# MCU.net
KiCad netlist of a schematic drawn in Altium Designer
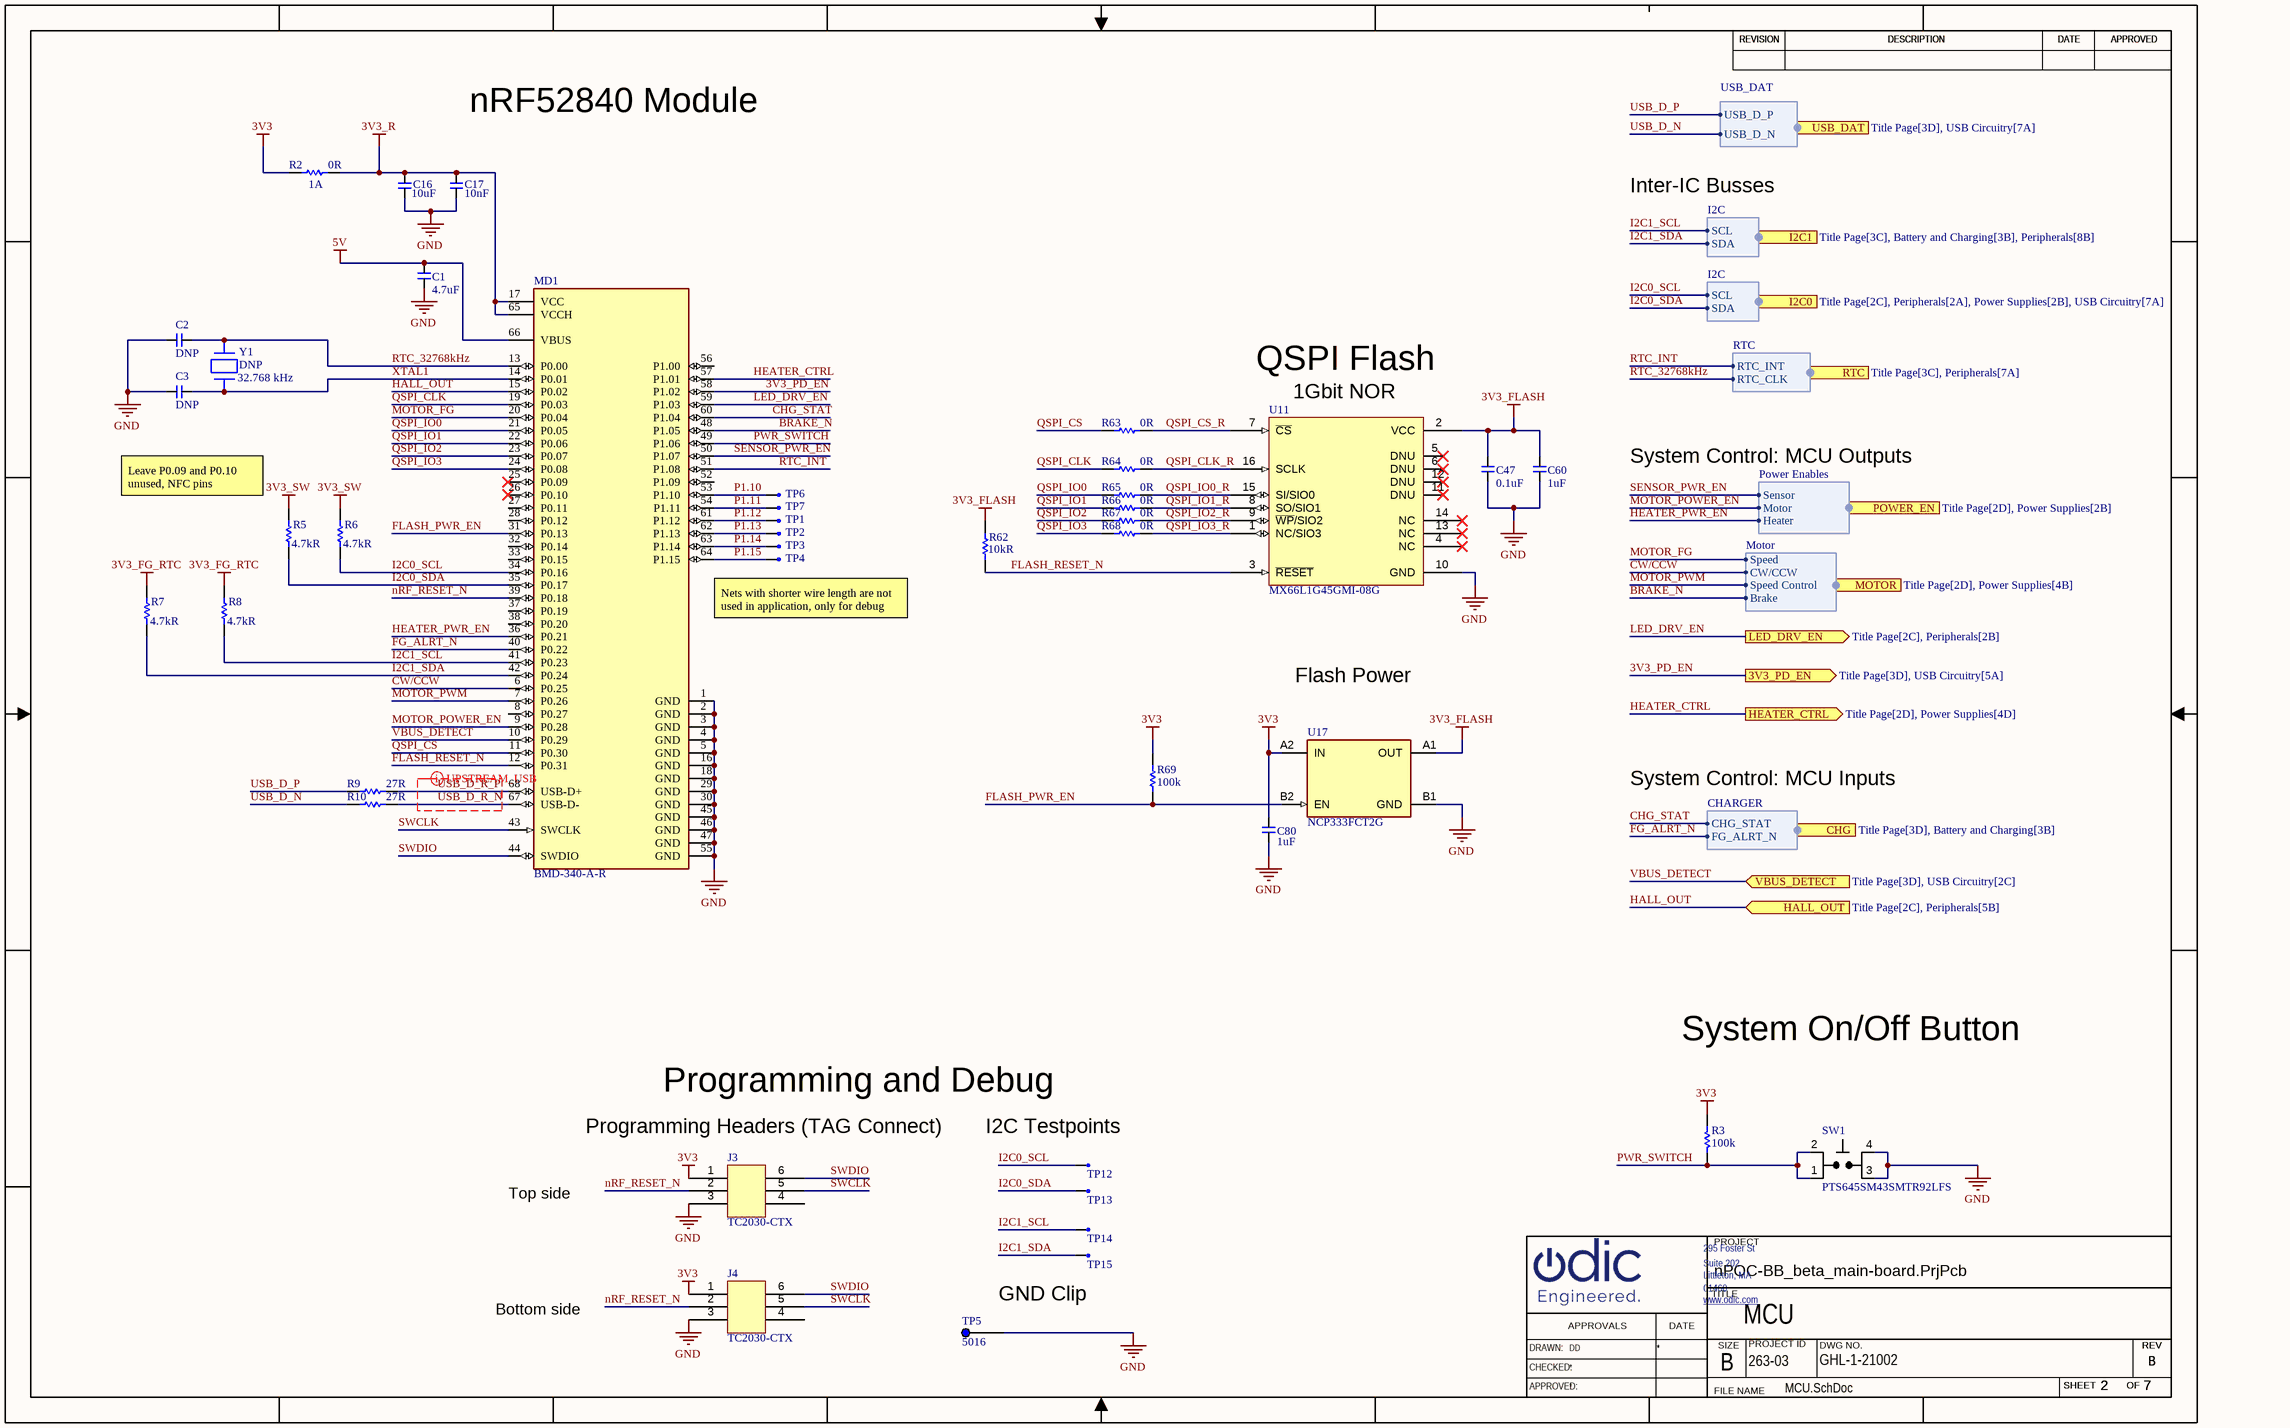
[diagram p0: MCU.SchDoc]

(export (version "E")
  (design (tool "Eeschema 10.0.6"))
  (components
    (comp (ref "C1")
      (value "4.7uF")
      (footprint "C0603")
      (description "CAP CER 4.7UF 25V X5R 0603")
      (fields (field (name "TOLERANCE") "20%"))
      (libsource (lib "Odic Inc") (part "cAP"))
    )
    (comp (ref "C2")
      (value "DNP")
      (footprint "C0402")
      (description "Blank pads for future cap placements")
      (libsource (lib "Odic Inc") (part "cAP"))
    )
    (comp (ref "C3")
      (value "DNP")
      (footprint "C0402")
      (description "Blank pads for future cap placements")
      (libsource (lib "Odic Inc") (part "cAP"))
    )
    (comp (ref "C16")
      (value "C0402_10u_6V3_20pct")
      (footprint "C0402")
      (description "Cap Ceramic 10uF 6.3V X5R 20% SMD 0402 85°C Paper T/R")
      (fields (field (name "CAPACITANCE") "10uF") (field (name "TOLERANCE") "20%"))
      (libsource (lib "Odic Inc") (part "cAP"))
    )
    (comp (ref "C17")
      (value "C0402_10n_6V3_10pct")
      (footprint "C0402")
      (description "CAP CER 10000PF 25V 10% X7R 0402")
      (fields
        (field (name "TOLERANCE") "10%")
        (field (name "CAPACITANCE") "10nF")
        (field (name "VOLTAGE") "25V")
      )
      (libsource (lib "Odic Inc") (part "cAP"))
    )
    (comp (ref "C47")
      (value "0.1uF")
      (footprint "C0402")
      (description "Cap Ceramic 0.1uF 25V X5R 10% Pad SMD 0402 Multi Layer Ceramic Capacitor (MLCC)")
      (fields (field (name "VOLTAGE") "25V") (field (name "TOLERANCE") "10%"))
      (libsource (lib "Odic Inc") (part "cAP"))
    )
    (comp (ref "C60")
      (value "1uF")
      (footprint "C0402")
      (description "CAP CER 1UF 16V X5R 0402")
      (fields (field (name "VOLTAGE") "16V") (field (name "TOLERANCE") "10%"))
      (libsource (lib "Odic Inc") (part "cAP"))
    )
    (comp (ref "C80")
      (value "C0402_1u_6V3_10pct")
      (footprint "C0402")
      (description "Cap Ceramic 1uF 6.3V X5R 10% SMD 0402 85C Paper T/R")
      (fields (field (name "CAPACITANCE") "1uF") (field (name "TOLERANCE") "10%"))
      (libsource (lib "Odic Inc") (part "cAP"))
    )
    (comp (ref "J3")
      (value "TC2030-CTX")
      (footprint "tc2030-ctx")
      (description "Cbl Plug-of-nails to Cortex Swd")
      (libsource (lib "Odic Inc") (part "TC2030-CTX-Symbol-1"))
    )
    (comp (ref "J4")
      (value "TC2030-CTX")
      (footprint "tc2030-ctx")
      (description "Cbl Plug-of-nails to Cortex Swd")
      (libsource (lib "Odic Inc") (part "TC2030-CTX-Symbol-1"))
    )
    (comp (ref "MD1")
      (value "BMD-340-A-R")
      (footprint "BMD-340-A-R")
      (description "BMD-340 Series 3.6 V 2.5 GHz -96 dBm Stand-Alone Bluetooth 5 Low Energy Module")
      (fields (field (name "MP") "BMD-330-A-R"))
      (libsource (lib "Odic Inc") (part "91e469dc995d0ea2fa1e7beafcd1398"))
    )
    (comp (ref "R2")
      (value "R0603_0R")
      (footprint "R0603")
      (description "Res Thkflm 0603 0 Ohm Jumper 1/10W 100Ppm/ C Smd Rohs Compliant: Yes")
      (fields (field (name "RESISTANCE") "0R") (field (name "CURRENT RATING") "1A"))
      (libsource (lib "Odic Inc") (part "RES"))
    )
    (comp (ref "R3")
      (value "100k")
      (footprint "R0402")
      (description "Res General Purpose Thick Film 0402 100K Ohm 1% 1/16W ±100ppm/°C Molded SMD Paper T/R")
      (fields (field (name "TOLERANCE") "1%"))
      (libsource (lib "Odic Inc") (part "RES"))
    )
    (comp (ref "R5")
      (value "R0402_4k7_1pct")
      (footprint "R0402")
      (description "RES 4.7K OHM 1% 1/16W 0402")
      (fields (field (name "TOLERANCE") "1%") (field (name "RESISTANCE") "4.7kR"))
      (libsource (lib "Odic Inc") (part "RES"))
    )
    (comp (ref "R6")
      (value "R0402_4k7_1pct")
      (footprint "R0402")
      (description "RES 4.7K OHM 1% 1/16W 0402")
      (fields (field (name "TOLERANCE") "1%") (field (name "RESISTANCE") "4.7kR"))
      (libsource (lib "Odic Inc") (part "RES"))
    )
    (comp (ref "R7")
      (value "R0402_4k7_1pct")
      (footprint "R0402")
      (description "RES 4.7K OHM 1% 1/16W 0402")
      (fields (field (name "TOLERANCE") "1%") (field (name "RESISTANCE") "4.7kR"))
      (libsource (lib "Odic Inc") (part "RES"))
    )
    (comp (ref "R8")
      (value "R0402_4k7_1pct")
      (footprint "R0402")
      (description "RES 4.7K OHM 1% 1/16W 0402")
      (fields (field (name "TOLERANCE") "1%") (field (name "RESISTANCE") "4.7kR"))
      (libsource (lib "Odic Inc") (part "RES"))
    )
    (comp (ref "R9")
      (value "27R")
      (footprint "R0402")
      (description "SMD Chip Resistor, 27 Ohm, ± 1%, 100 mW, 0402 [1005 Metric], Thick Film, Precision")
      (fields (field (name "TOLERANCE") "1%"))
      (libsource (lib "Odic Inc") (part "RES"))
    )
    (comp (ref "R10")
      (value "27R")
      (footprint "R0402")
      (description "SMD Chip Resistor, 27 Ohm, ± 1%, 100 mW, 0402 [1005 Metric], Thick Film, Precision")
      (fields (field (name "TOLERANCE") "1%"))
      (libsource (lib "Odic Inc") (part "RES"))
    )
    (comp (ref "R62")
      (value "R0402_10k_1pct")
      (footprint "R0402")
      (description "Res Thick Film 0402 10K Ohm 1% 1/16W ±100ppm/°C Molded SMD SMD T/R")
      (fields (field (name "RESISTANCE") "10kR") (field (name "TOLERANCE") "1%"))
      (libsource (lib "Odic Inc") (part "RES"))
    )
    (comp (ref "R63")
      (value "0R")
      (footprint "R0402")
      (description "RES 0 OHM JUMPER 1/16W 0402")
      (libsource (lib "Odic Inc") (part "RES"))
    )
    (comp (ref "R64")
      (value "0R")
      (footprint "R0402")
      (description "RES 0 OHM JUMPER 1/16W 0402")
      (libsource (lib "Odic Inc") (part "RES"))
    )
    (comp (ref "R65")
      (value "0R")
      (footprint "R0402")
      (description "RES 0 OHM JUMPER 1/16W 0402")
      (libsource (lib "Odic Inc") (part "RES"))
    )
    (comp (ref "R66")
      (value "0R")
      (footprint "R0402")
      (description "RES 0 OHM JUMPER 1/16W 0402")
      (libsource (lib "Odic Inc") (part "RES"))
    )
    (comp (ref "R67")
      (value "0R")
      (footprint "R0402")
      (description "RES 0 OHM JUMPER 1/16W 0402")
      (libsource (lib "Odic Inc") (part "RES"))
    )
    (comp (ref "R68")
      (value "0R")
      (footprint "R0402")
      (description "RES 0 OHM JUMPER 1/16W 0402")
      (libsource (lib "Odic Inc") (part "RES"))
    )
    (comp (ref "R69")
      (value "100k")
      (footprint "R0402")
      (description "Res General Purpose Thick Film 0402 100K Ohm 1% 1/16W ±100ppm/°C Molded SMD Paper T/R")
      (fields (field (name "TOLERANCE") "1%"))
      (libsource (lib "Odic Inc") (part "RES"))
    )
    (comp (ref "SW1")
      (value "PTS645SM43SMTR92LFS")
      (footprint "swt_pb_pts645s")
      (description "Switch Tactile N.O. SPST Round Button Gull Wing 0.05A 12VDC 100000Cycles 1.57N SMD T/R")
      (libsource (lib "Odic Inc") (part "TL3315NF160Q-Symbol-1"))
    )
    (comp (ref "TP1")
      (value "TPC30")
      (footprint "tpc30")
      (description "Test Point Circle 30")
      (libsource (lib "Odic Inc") (part "TPC"))
    )
    (comp (ref "TP2")
      (value "TPC30")
      (footprint "tpc30")
      (description "Test Point Circle 30")
      (libsource (lib "Odic Inc") (part "TPC"))
    )
    (comp (ref "TP3")
      (value "TPC30")
      (footprint "tpc30")
      (description "Test Point Circle 30")
      (libsource (lib "Odic Inc") (part "TPC"))
    )
    (comp (ref "TP4")
      (value "TPC30")
      (footprint "tpc30")
      (description "Test Point Circle 30")
      (libsource (lib "Odic Inc") (part "TPC"))
    )
    (comp (ref "TP5")
      (value "5016")
      (footprint "KEYSTONE_5016")
      (description "Test point clip, SMT Phos Bronze/Silver 1000pc Tape & Reel")
      (libsource (lib "Odic Inc") (part "5016-Symbol-1"))
    )
    (comp (ref "TP6")
      (value "TPC30")
      (footprint "tpc30")
      (description "Test Point Circle 30")
      (libsource (lib "Odic Inc") (part "TPC"))
    )
    (comp (ref "TP7")
      (value "TPC30")
      (footprint "tpc30")
      (description "Test Point Circle 30")
      (libsource (lib "Odic Inc") (part "TPC"))
    )
    (comp (ref "TP12")
      (value "TPC30")
      (footprint "tpc30")
      (description "Test Point Circle 30")
      (libsource (lib "Odic Inc") (part "TPC"))
    )
    (comp (ref "TP13")
      (value "TPC30")
      (footprint "tpc30")
      (description "Test Point Circle 30")
      (libsource (lib "Odic Inc") (part "TPC"))
    )
    (comp (ref "TP14")
      (value "TPC30")
      (footprint "tpc30")
      (description "Test Point Circle 30")
      (libsource (lib "Odic Inc") (part "TPC"))
    )
    (comp (ref "TP15")
      (value "TPC30")
      (footprint "tpc30")
      (description "Test Point Circle 30")
      (libsource (lib "Odic Inc") (part "TPC"))
    )
    (comp (ref "U11")
      (value "MX66L1G45GMI-08G")
      (footprint "sol16")
      (description "MX66L1G45G Series 1 Gb (1 G x 1) 2.7 - 3.6 V SMT Serial Flash Memory - SOP-16")
      (libsource (lib "Odic Inc") (part "MX66L1G45GMI-08G-Symbol-1"))
    )
    (comp (ref "U17")
      (value "NCP333FCT2G")
      (footprint "bga4_p743xp743_p4mm")
      (description "IC LOAD SWITCH W/DIS 1.5A 4WLCSP")
      (libsource (lib "Odic Inc") (part "97019fd276bc7644be76e1f711e9589"))
    )
    (comp (ref "Y1")
      (value "DNP")
      (footprint "xtal2_3p2x1p5")
      (description "RT3215 Series 0.032768 ±20 ppm 9pF -40°C TO +85°C SMT Tuning Fork Crystal")
      (fields (field (name "OPERATING FREQUENCY") "32.768 kHz"))
      (libsource (lib "Odic Inc") (part "Y*"))
    )
  )
  (nets
    (net (code "8") (name "/3V3_PD_EN") (class "Default")
      (node (ref "MD1") (pin "58") (pinfunction "P1.02_58") (pintype "bidirectional"))
    )
    (net (code "9") (name "/BRAKE_N") (class "Default")
      (node (ref "MD1") (pin "48") (pinfunction "P1.05_48") (pintype "bidirectional"))
    )
    (net (code "10") (name "/CHG_STAT") (class "Default")
      (node (ref "MD1") (pin "60") (pinfunction "P1.04_60") (pintype "bidirectional"))
    )
    (net (code "11") (name "/CW{slash}CCW") (class "Default")
      (node (ref "MD1") (pin "6") (pinfunction "P0.25_6") (pintype "bidirectional"))
    )
    (net (code "12") (name "/FG_ALRT_N") (class "Default")
      (node (ref "MD1") (pin "40") (pinfunction "P0.22_40") (pintype "bidirectional"))
    )
    (net (code "13") (name "/FLASH_PWR_EN") (class "Default")
      (node (ref "MD1") (pin "31") (pinfunction "P0.13_31") (pintype "bidirectional"))
      (node (ref "R69") (pin "2") (pinfunction "2_2") (pintype "passive"))
      (node (ref "U17") (pin "B2") (pinfunction "EN_B2") (pintype "input"))
    )
    (net (code "14") (name "/FLASH_RESET_N") (class "Default")
      (node (ref "MD1") (pin "12") (pinfunction "P0.31_12") (pintype "bidirectional"))
      (node (ref "R62") (pin "2") (pinfunction "2_2") (pintype "passive"))
      (node (ref "U11") (pin "3") (pinfunction "~{RESET}_3") (pintype "input"))
    )
    (net (code "15") (name "/HALL_OUT") (class "Default")
      (node (ref "MD1") (pin "15") (pinfunction "P0.02_15") (pintype "bidirectional"))
    )
    (net (code "16") (name "/HEATER_CTRL") (class "Default")
      (node (ref "MD1") (pin "57") (pinfunction "P1.01_57") (pintype "bidirectional"))
    )
    (net (code "17") (name "/HEATER_PWR_EN") (class "Default")
      (node (ref "MD1") (pin "36") (pinfunction "P0.21_36") (pintype "bidirectional"))
    )
    (net (code "18") (name "/I2C0_SCL") (class "Default")
      (node (ref "MD1") (pin "34") (pinfunction "P0.16_34") (pintype "bidirectional"))
      (node (ref "R6") (pin "1") (pinfunction "1_1") (pintype "passive"))
      (node (ref "TP12") (pin "1") (pinfunction "1_1") (pintype "passive"))
    )
    (net (code "19") (name "/I2C0_SDA") (class "Default")
      (node (ref "MD1") (pin "35") (pinfunction "P0.17_35") (pintype "bidirectional"))
      (node (ref "R5") (pin "1") (pinfunction "1_1") (pintype "passive"))
      (node (ref "TP13") (pin "1") (pinfunction "1_1") (pintype "passive"))
    )
    (net (code "20") (name "/I2C1_SCL") (class "Default")
      (node (ref "MD1") (pin "41") (pinfunction "P0.23_41") (pintype "bidirectional"))
      (node (ref "R8") (pin "1") (pinfunction "1_1") (pintype "passive"))
      (node (ref "TP14") (pin "1") (pinfunction "1_1") (pintype "passive"))
    )
    (net (code "21") (name "/I2C1_SDA") (class "Default")
      (node (ref "MD1") (pin "42") (pinfunction "P0.24_42") (pintype "bidirectional"))
      (node (ref "R7") (pin "1") (pinfunction "1_1") (pintype "passive"))
      (node (ref "TP15") (pin "1") (pinfunction "1_1") (pintype "passive"))
    )
    (net (code "22") (name "/LED_DRV_EN") (class "Default")
      (node (ref "MD1") (pin "59") (pinfunction "P1.03_59") (pintype "bidirectional"))
    )
    (net (code "23") (name "/MOTOR_FG") (class "Default")
      (node (ref "MD1") (pin "20") (pinfunction "P0.04_20") (pintype "bidirectional"))
    )
    (net (code "24") (name "/MOTOR_POWER_EN") (class "Default")
      (node (ref "MD1") (pin "9") (pinfunction "P0.28_9") (pintype "bidirectional"))
    )
    (net (code "25") (name "/MOTOR_PWM") (class "Default")
      (node (ref "MD1") (pin "7") (pinfunction "P0.26_7") (pintype "bidirectional"))
    )
    (net (code "26") (name "/P1.10") (class "Default")
      (node (ref "MD1") (pin "53") (pinfunction "P1.10_53") (pintype "bidirectional"))
      (node (ref "TP6") (pin "1") (pinfunction "1_1") (pintype "passive"))
    )
    (net (code "27") (name "/P1.11") (class "Default")
      (node (ref "MD1") (pin "54") (pinfunction "P1.11_54") (pintype "bidirectional"))
      (node (ref "TP7") (pin "1") (pinfunction "1_1") (pintype "passive"))
    )
    (net (code "28") (name "/P1.12") (class "Default")
      (node (ref "MD1") (pin "61") (pinfunction "P1.12_61") (pintype "bidirectional"))
      (node (ref "TP1") (pin "1") (pinfunction "1_1") (pintype "passive"))
    )
    (net (code "29") (name "/P1.13") (class "Default")
      (node (ref "MD1") (pin "62") (pinfunction "P1.13_62") (pintype "bidirectional"))
      (node (ref "TP2") (pin "1") (pinfunction "1_1") (pintype "passive"))
    )
    (net (code "30") (name "/P1.14") (class "Default")
      (node (ref "MD1") (pin "63") (pinfunction "P1.14_63") (pintype "bidirectional"))
      (node (ref "TP3") (pin "1") (pinfunction "1_1") (pintype "passive"))
    )
    (net (code "31") (name "/P1.15") (class "Default")
      (node (ref "MD1") (pin "64") (pinfunction "P1.15_64") (pintype "bidirectional"))
      (node (ref "TP4") (pin "1") (pinfunction "1_1") (pintype "passive"))
    )
    (net (code "32") (name "/PWR_SWITCH") (class "Default")
      (node (ref "MD1") (pin "49") (pinfunction "P1.06_49") (pintype "bidirectional"))
      (node (ref "R3") (pin "1") (pinfunction "1_1") (pintype "passive"))
      (node (ref "SW1") (pin "1") (pinfunction "1_1") (pintype "passive"))
      (node (ref "SW1") (pin "2") (pinfunction "2_2") (pintype "passive"))
    )
    (net (code "33") (name "/QSPI_CLK") (class "Default")
      (node (ref "MD1") (pin "19") (pinfunction "P0.03_19") (pintype "bidirectional"))
      (node (ref "R64") (pin "1") (pinfunction "1_1") (pintype "passive"))
    )
    (net (code "34") (name "/QSPI_CLK_R") (class "Default")
      (node (ref "R64") (pin "2") (pinfunction "2_2") (pintype "passive"))
      (node (ref "U11") (pin "16") (pinfunction "SCLK_16") (pintype "input"))
    )
    (net (code "35") (name "/QSPI_CS") (class "Default")
      (node (ref "MD1") (pin "11") (pinfunction "P0.30_11") (pintype "bidirectional"))
      (node (ref "R63") (pin "1") (pinfunction "1_1") (pintype "passive"))
    )
    (net (code "36") (name "/QSPI_CS_R") (class "Default")
      (node (ref "R63") (pin "2") (pinfunction "2_2") (pintype "passive"))
      (node (ref "U11") (pin "7") (pinfunction "~{CS}_7") (pintype "input"))
    )
    (net (code "37") (name "/QSPI_IO0") (class "Default")
      (node (ref "MD1") (pin "21") (pinfunction "P0.05_21") (pintype "bidirectional"))
      (node (ref "R65") (pin "1") (pinfunction "1_1") (pintype "passive"))
    )
    (net (code "38") (name "/QSPI_IO0_R") (class "Default")
      (node (ref "R65") (pin "2") (pinfunction "2_2") (pintype "passive"))
      (node (ref "U11") (pin "15") (pinfunction "SI/SIO0_15") (pintype "bidirectional"))
    )
    (net (code "39") (name "/QSPI_IO1") (class "Default")
      (node (ref "MD1") (pin "22") (pinfunction "P0.06_22") (pintype "bidirectional"))
      (node (ref "R66") (pin "1") (pinfunction "1_1") (pintype "passive"))
    )
    (net (code "40") (name "/QSPI_IO1_R") (class "Default")
      (node (ref "R66") (pin "2") (pinfunction "2_2") (pintype "passive"))
      (node (ref "U11") (pin "8") (pinfunction "SO/SIO1_8") (pintype "bidirectional"))
    )
    (net (code "41") (name "/QSPI_IO2") (class "Default")
      (node (ref "MD1") (pin "23") (pinfunction "P0.07_23") (pintype "bidirectional"))
      (node (ref "R67") (pin "1") (pinfunction "1_1") (pintype "passive"))
    )
    (net (code "42") (name "/QSPI_IO2_R") (class "Default")
      (node (ref "R67") (pin "2") (pinfunction "2_2") (pintype "passive"))
      (node (ref "U11") (pin "9") (pinfunction "~{WP}/SIO2_9") (pintype "bidirectional"))
    )
    (net (code "43") (name "/QSPI_IO3") (class "Default")
      (node (ref "MD1") (pin "24") (pinfunction "P0.08_24") (pintype "bidirectional"))
      (node (ref "R68") (pin "1") (pinfunction "1_1") (pintype "passive"))
    )
    (net (code "44") (name "/QSPI_IO3_R") (class "Default")
      (node (ref "R68") (pin "2") (pinfunction "2_2") (pintype "passive"))
      (node (ref "U11") (pin "1") (pinfunction "NC/SIO3_1") (pintype "bidirectional"))
    )
    (net (code "45") (name "/RTC_32768kHz") (class "Default")
      (node (ref "C2") (pin "2") (pinfunction "2_2") (pintype "passive"))
      (node (ref "MD1") (pin "13") (pinfunction "P0.00_13") (pintype "bidirectional"))
      (node (ref "Y1") (pin "1") (pinfunction "1_1") (pintype "passive"))
    )
    (net (code "46") (name "/RTC_INT") (class "Default")
      (node (ref "MD1") (pin "51") (pinfunction "P1.08_51") (pintype "bidirectional"))
    )
    (net (code "47") (name "/SENSOR_PWR_EN") (class "Default")
      (node (ref "MD1") (pin "50") (pinfunction "P1.07_50") (pintype "bidirectional"))
    )
    (net (code "48") (name "/SWCLK") (class "Default")
      (node (ref "J3") (pin "5") (pinfunction "5_5") (pintype "passive"))
      (node (ref "J4") (pin "5") (pinfunction "5_5") (pintype "passive"))
      (node (ref "MD1") (pin "43") (pinfunction "SWCLK_43") (pintype "input"))
    )
    (net (code "49") (name "/SWDIO") (class "Default")
      (node (ref "J3") (pin "6") (pinfunction "6_6") (pintype "passive"))
      (node (ref "J4") (pin "6") (pinfunction "6_6") (pintype "passive"))
      (node (ref "MD1") (pin "44") (pinfunction "SWDIO_44") (pintype "bidirectional"))
    )
    (net (code "50") (name "/USB_D_N") (class "Default")
      (node (ref "R10") (pin "1") (pinfunction "1_1") (pintype "passive"))
    )
    (net (code "51") (name "/USB_D_P") (class "Default")
      (node (ref "R9") (pin "1") (pinfunction "1_1") (pintype "passive"))
    )
    (net (code "52") (name "/USB_D_R_N") (class "Default")
      (node (ref "MD1") (pin "67") (pinfunction "USB-D-_67") (pintype "bidirectional"))
      (node (ref "R10") (pin "2") (pinfunction "2_2") (pintype "passive"))
    )
    (net (code "53") (name "/USB_D_R_P") (class "Default")
      (node (ref "MD1") (pin "68") (pinfunction "USB-D+_68") (pintype "bidirectional"))
      (node (ref "R9") (pin "2") (pinfunction "2_2") (pintype "passive"))
    )
    (net (code "54") (name "/VBUS_DETECT") (class "Default")
      (node (ref "MD1") (pin "10") (pinfunction "P0.29_10") (pintype "bidirectional"))
    )
    (net (code "55") (name "/XTAL1") (class "Default")
      (node (ref "C3") (pin "2") (pinfunction "2_2") (pintype "passive"))
      (node (ref "MD1") (pin "14") (pinfunction "P0.01_14") (pintype "bidirectional"))
      (node (ref "Y1") (pin "2") (pinfunction "2_2") (pintype "passive"))
    )
    (net (code "56") (name "/nRF_RESET_N") (class "Default")
      (node (ref "J3") (pin "2") (pinfunction "2_2") (pintype "passive"))
      (node (ref "J4") (pin "2") (pinfunction "2_2") (pintype "passive"))
      (node (ref "MD1") (pin "39") (pinfunction "P0.18_39") (pintype "bidirectional"))
    )
    (net (code "63") (name "3V3") (class "Default")
      (node (ref "C80") (pin "2") (pinfunction "2_2") (pintype "passive"))
      (node (ref "J3") (pin "1") (pinfunction "1_1") (pintype "passive"))
      (node (ref "J4") (pin "1") (pinfunction "1_1") (pintype "passive"))
      (node (ref "R2") (pin "1") (pinfunction "1_1") (pintype "passive"))
      (node (ref "R3") (pin "2") (pinfunction "2_2") (pintype "passive"))
      (node (ref "R69") (pin "1") (pinfunction "1_1") (pintype "passive"))
      (node (ref "U17") (pin "A2") (pinfunction "IN_A2") (pintype "power_in"))
    )
    (net (code "64") (name "3V3_FG_RTC") (class "Default")
      (node (ref "R7") (pin "2") (pinfunction "2_2") (pintype "passive"))
      (node (ref "R8") (pin "2") (pinfunction "2_2") (pintype "passive"))
    )
    (net (code "65") (name "3V3_FLASH") (class "Default")
      (node (ref "C47") (pin "2") (pinfunction "2_2") (pintype "passive"))
      (node (ref "C60") (pin "2") (pinfunction "2_2") (pintype "passive"))
      (node (ref "R62") (pin "1") (pinfunction "1_1") (pintype "passive"))
      (node (ref "U11") (pin "2") (pinfunction "VCC_2") (pintype "power_in"))
      (node (ref "U17") (pin "A1") (pinfunction "OUT_A1") (pintype "power_in"))
    )
    (net (code "66") (name "3V3_R") (class "Default")
      (node (ref "C16") (pin "2") (pinfunction "2_2") (pintype "passive"))
      (node (ref "C17") (pin "2") (pinfunction "2_2") (pintype "passive"))
      (node (ref "MD1") (pin "17") (pinfunction "VCC_17") (pintype "power_in"))
      (node (ref "MD1") (pin "65") (pinfunction "VCCH_65") (pintype "power_in"))
      (node (ref "R2") (pin "2") (pinfunction "2_2") (pintype "passive"))
    )
    (net (code "67") (name "3V3_SW") (class "Default")
      (node (ref "R5") (pin "2") (pinfunction "2_2") (pintype "passive"))
      (node (ref "R6") (pin "2") (pinfunction "2_2") (pintype "passive"))
    )
    (net (code "68") (name "5V") (class "Default")
      (node (ref "C1") (pin "2") (pinfunction "2_2") (pintype "passive"))
      (node (ref "MD1") (pin "66") (pinfunction "VBUS_66") (pintype "power_in"))
    )
    (net (code "69") (name "GND") (class "Default")
      (node (ref "C1") (pin "1") (pinfunction "1_1") (pintype "passive"))
      (node (ref "C16") (pin "1") (pinfunction "1_1") (pintype "passive"))
      (node (ref "C17") (pin "1") (pinfunction "1_1") (pintype "passive"))
      (node (ref "C2") (pin "1") (pinfunction "1_1") (pintype "passive"))
      (node (ref "C3") (pin "1") (pinfunction "1_1") (pintype "passive"))
      (node (ref "C47") (pin "1") (pinfunction "1_1") (pintype "passive"))
      (node (ref "C60") (pin "1") (pinfunction "1_1") (pintype "passive"))
      (node (ref "C80") (pin "1") (pinfunction "1_1") (pintype "passive"))
      (node (ref "J3") (pin "3") (pinfunction "3_3") (pintype "passive"))
      (node (ref "J4") (pin "3") (pinfunction "3_3") (pintype "passive"))
      (node (ref "MD1") (pin "1") (pinfunction "GND_1") (pintype "power_in"))
      (node (ref "MD1") (pin "16") (pinfunction "GND_16") (pintype "power_in"))
      (node (ref "MD1") (pin "18") (pinfunction "GND_18") (pintype "power_in"))
      (node (ref "MD1") (pin "2") (pinfunction "GND_2") (pintype "power_in"))
      (node (ref "MD1") (pin "29") (pinfunction "GND_29") (pintype "power_in"))
      (node (ref "MD1") (pin "3") (pinfunction "GND_3") (pintype "power_in"))
      (node (ref "MD1") (pin "30") (pinfunction "GND_30") (pintype "power_in"))
      (node (ref "MD1") (pin "4") (pinfunction "GND_4") (pintype "power_in"))
      (node (ref "MD1") (pin "45") (pinfunction "GND_45") (pintype "power_in"))
      (node (ref "MD1") (pin "46") (pinfunction "GND_46") (pintype "power_in"))
      (node (ref "MD1") (pin "47") (pinfunction "GND_47") (pintype "power_in"))
      (node (ref "MD1") (pin "5") (pinfunction "GND_5") (pintype "power_in"))
      (node (ref "MD1") (pin "55") (pinfunction "GND_55") (pintype "power_in"))
      (node (ref "SW1") (pin "3") (pinfunction "3_3") (pintype "passive"))
      (node (ref "SW1") (pin "4") (pinfunction "4_4") (pintype "passive"))
      (node (ref "TP5") (pin "1") (pinfunction "1_1") (pintype "passive"))
      (node (ref "U11") (pin "10") (pinfunction "GND_10") (pintype "passive"))
      (node (ref "U17") (pin "B1") (pinfunction "GND_B1") (pintype "power_in"))
    )
    (net (code "70") (name "unconnected-(J3-Pad4)") (class "Default")
      (node (ref "J3") (pin "4") (pinfunction "4_4") (pintype "passive"))
    )
    (net (code "71") (name "unconnected-(J4-Pad4)") (class "Default")
      (node (ref "J4") (pin "4") (pinfunction "4_4") (pintype "passive"))
    )
    (net (code "72") (name "unconnected-(MD1-P0.09-Pad25)") (class "Default")
      (node (ref "MD1") (pin "25") (pinfunction "P0.09_25") (pintype "bidirectional+no_connect"))
    )
    (net (code "73") (name "unconnected-(MD1-P0.10-Pad26)") (class "Default")
      (node (ref "MD1") (pin "26") (pinfunction "P0.10_26") (pintype "bidirectional+no_connect"))
    )
    (net (code "74") (name "unconnected-(MD1-P0.11-Pad27)") (class "Default")
      (node (ref "MD1") (pin "27") (pinfunction "P0.11_27") (pintype "bidirectional"))
    )
    (net (code "75") (name "unconnected-(MD1-P0.12-Pad28)") (class "Default")
      (node (ref "MD1") (pin "28") (pinfunction "P0.12_28") (pintype "bidirectional"))
    )
    (net (code "76") (name "unconnected-(MD1-P0.14-Pad32)") (class "Default")
      (node (ref "MD1") (pin "32") (pinfunction "P0.14_32") (pintype "bidirectional"))
    )
    (net (code "77") (name "unconnected-(MD1-P0.15-Pad33)") (class "Default")
      (node (ref "MD1") (pin "33") (pinfunction "P0.15_33") (pintype "bidirectional"))
    )
    (net (code "78") (name "unconnected-(MD1-P0.19-Pad37)") (class "Default")
      (node (ref "MD1") (pin "37") (pinfunction "P0.19_37") (pintype "bidirectional"))
    )
    (net (code "79") (name "unconnected-(MD1-P0.20-Pad38)") (class "Default")
      (node (ref "MD1") (pin "38") (pinfunction "P0.20_38") (pintype "bidirectional"))
    )
    (net (code "80") (name "unconnected-(MD1-P0.27-Pad8)") (class "Default")
      (node (ref "MD1") (pin "8") (pinfunction "P0.27_8") (pintype "bidirectional"))
    )
    (net (code "81") (name "unconnected-(MD1-P1.00-Pad56)") (class "Default")
      (node (ref "MD1") (pin "56") (pinfunction "P1.00_56") (pintype "bidirectional"))
    )
    (net (code "82") (name "unconnected-(MD1-P1.09-Pad52)") (class "Default")
      (node (ref "MD1") (pin "52") (pinfunction "P1.09_52") (pintype "bidirectional"))
    )
    (net (code "83") (name "unconnected-(U11-DNU-Pad5)") (class "Default")
      (node (ref "U11") (pin "5") (pinfunction "DNU_5") (pintype "passive+no_connect"))
    )
    (net (code "84") (name "unconnected-(U11-DNU-Pad6)") (class "Default")
      (node (ref "U11") (pin "6") (pinfunction "DNU_6") (pintype "passive+no_connect"))
    )
    (net (code "85") (name "unconnected-(U11-DNU-Pad11)") (class "Default")
      (node (ref "U11") (pin "11") (pinfunction "DNU_11") (pintype "passive+no_connect"))
    )
    (net (code "86") (name "unconnected-(U11-DNU-Pad12)") (class "Default")
      (node (ref "U11") (pin "12") (pinfunction "DNU_12") (pintype "passive+no_connect"))
    )
    (net (code "87") (name "unconnected-(U11-NC-Pad4)") (class "Default")
      (node (ref "U11") (pin "4") (pinfunction "NC_4") (pintype "passive+no_connect"))
    )
    (net (code "88") (name "unconnected-(U11-NC-Pad13)") (class "Default")
      (node (ref "U11") (pin "13") (pinfunction "NC_13") (pintype "passive+no_connect"))
    )
    (net (code "89") (name "unconnected-(U11-NC-Pad14)") (class "Default")
      (node (ref "U11") (pin "14") (pinfunction "NC_14") (pintype "passive+no_connect"))
    )
  )
)
